# FIT_HDMI_X24-20.net
KiCad netlist of a schematic drawn in Altium Designer
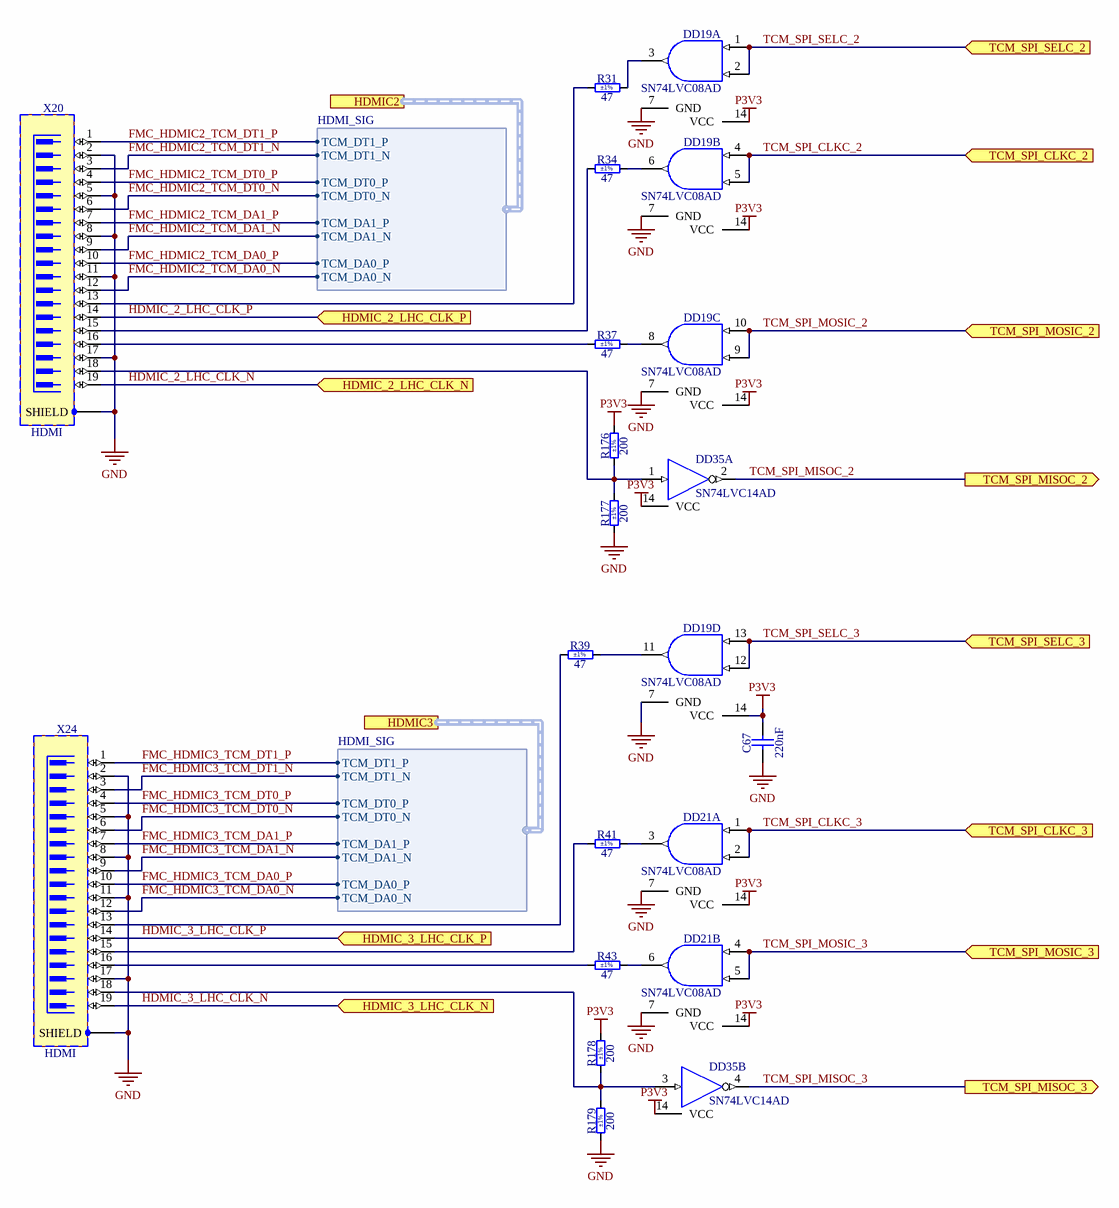
[diagram p0: FIT_HDMI_X24-20.SchDoc]

(export (version "E")
  (design (tool "Eeschema 10.0.6"))
  (components
    (comp (ref "C67")
      (value "220nF")
      (footprint "CAPC2012X135N")
      (description "Non-polarised capacitor")
      (fields
        (field (name "PART NUMBER") "CC0805_220NF_50V_10%_X7R")
        (field (name "VOLTAGE") "50V")
        (field (name "AUTHOR") "CERN DEM JLC")
      )
      (libsource (lib "Capacitors") (part "Capacitor - non polarized"))
    )
    (comp (ref "DD19")
      (value "SN74LVC08AD")
      (footprint "SOIC127P600X175-14N")
      (description "Quad 2-Input AND Gate")
      (fields (field (name "MANUFACTURER") "TEXAS INSTRUMENTS") (field (name "AUTHOR") "CERN DEM JLC"))
      (libsource (lib "ICs And Semiconductors") (part "7408"))
    )
    (comp (ref "DD21")
      (value "SN74LVC08AD")
      (footprint "SOIC127P600X175-14N")
      (description "Quad 2-Input AND Gate")
      (fields (field (name "MANUFACTURER") "TEXAS INSTRUMENTS") (field (name "AUTHOR") "CERN DEM JLC"))
      (libsource (lib "ICs And Semiconductors") (part "7408"))
    )
    (comp (ref "DD35")
      (value "SN74LVC14AD")
      (footprint "SOIC127P600X175-14N")
      (description "Hex Schmitt-Trigger Inverter")
      (fields (field (name "MANUFACTURER") "TEXAS INSTRUMENTS") (field (name "AUTHOR") "CERN DEM JMW"))
      (libsource (lib "ICs And Semiconductors") (part "7414"))
    )
    (comp (ref "R31")
      (value "47")
      (footprint "RESC2012X60N")
      (description "Resistor - 1%")
      (fields
        (field (name "TOLERANCE") "±1%")
        (field (name "PART NUMBER") "R0805_47R_1%_0.125W_100PPM")
        (field (name "POWER") "0.125W")
        (field (name "AUTHOR") "CERN DEM JLC")
      )
      (libsource (lib "Resistors") (part "Resistor - 1%"))
    )
    (comp (ref "R34")
      (value "47")
      (footprint "RESC2012X60N")
      (description "Resistor - 1%")
      (fields
        (field (name "TOLERANCE") "±1%")
        (field (name "PART NUMBER") "R0805_47R_1%_0.125W_100PPM")
        (field (name "POWER") "0.125W")
        (field (name "AUTHOR") "CERN DEM JLC")
      )
      (libsource (lib "Resistors") (part "Resistor - 1%"))
    )
    (comp (ref "R37")
      (value "47")
      (footprint "RESC2012X60N")
      (description "Resistor - 1%")
      (fields
        (field (name "TOLERANCE") "±1%")
        (field (name "PART NUMBER") "R0805_47R_1%_0.125W_100PPM")
        (field (name "POWER") "0.125W")
        (field (name "AUTHOR") "CERN DEM JLC")
      )
      (libsource (lib "Resistors") (part "Resistor - 1%"))
    )
    (comp (ref "R39")
      (value "47")
      (footprint "RESC2012X60N")
      (description "Resistor - 1%")
      (fields
        (field (name "TOLERANCE") "±1%")
        (field (name "PART NUMBER") "R0805_47R_1%_0.125W_100PPM")
        (field (name "POWER") "0.125W")
        (field (name "AUTHOR") "CERN DEM JLC")
      )
      (libsource (lib "Resistors") (part "Resistor - 1%"))
    )
    (comp (ref "R41")
      (value "47")
      (footprint "RESC2012X60N")
      (description "Resistor - 1%")
      (fields
        (field (name "TOLERANCE") "±1%")
        (field (name "PART NUMBER") "R0805_47R_1%_0.125W_100PPM")
        (field (name "POWER") "0.125W")
        (field (name "AUTHOR") "CERN DEM JLC")
      )
      (libsource (lib "Resistors") (part "Resistor - 1%"))
    )
    (comp (ref "R43")
      (value "47")
      (footprint "RESC2012X60N")
      (description "Resistor - 1%")
      (fields
        (field (name "TOLERANCE") "±1%")
        (field (name "PART NUMBER") "R0805_47R_1%_0.125W_100PPM")
        (field (name "POWER") "0.125W")
        (field (name "AUTHOR") "CERN DEM JLC")
      )
      (libsource (lib "Resistors") (part "Resistor - 1%"))
    )
    (comp (ref "R176")
      (value "200")
      (footprint "RESC2012X60N")
      (description "Resistor - 1%")
      (fields
        (field (name "TOLERANCE") "±1%")
        (field (name "PART NUMBER") "R0805_200R_1%_0.125W_100PPM")
        (field (name "POWER") "0.125W")
        (field (name "AUTHOR") "CERN DEM JLC")
      )
      (libsource (lib "Resistors") (part "Resistor - 1%"))
    )
    (comp (ref "R177")
      (value "200")
      (footprint "RESC2012X60N")
      (description "Resistor - 1%")
      (fields
        (field (name "TOLERANCE") "±1%")
        (field (name "PART NUMBER") "R0805_200R_1%_0.125W_100PPM")
        (field (name "POWER") "0.125W")
        (field (name "AUTHOR") "CERN DEM JLC")
      )
      (libsource (lib "Resistors") (part "Resistor - 1%"))
    )
    (comp (ref "R178")
      (value "200")
      (footprint "RESC2012X60N")
      (description "Resistor - 1%")
      (fields
        (field (name "TOLERANCE") "±1%")
        (field (name "PART NUMBER") "R0805_200R_1%_0.125W_100PPM")
        (field (name "POWER") "0.125W")
        (field (name "AUTHOR") "CERN DEM JLC")
      )
      (libsource (lib "Resistors") (part "Resistor - 1%"))
    )
    (comp (ref "R179")
      (value "200")
      (footprint "RESC2012X60N")
      (description "Resistor - 1%")
      (fields
        (field (name "TOLERANCE") "±1%")
        (field (name "PART NUMBER") "R0805_200R_1%_0.125W_100PPM")
        (field (name "POWER") "0.125W")
        (field (name "AUTHOR") "CERN DEM JLC")
      )
      (libsource (lib "Resistors") (part "Resistor - 1%"))
    )
    (comp (ref "X20")
      (value "HDMI")
      (footprint "TYCO_2007435-1")
      (description "Connector HDMI 19 Male + 1 Shield")
      (fields
        (field (name "PART NUMBER") "TYCO_2007435-1")
        (field (name "MANUFACTURER") "TYCO ELECTRONICS")
        (field (name "AUTHOR") "CERN DEM MR")
      )
      (libsource (lib "Connectors") (part "Connector HDMI 19 Male + 1 Shield"))
    )
    (comp (ref "X24")
      (value "HDMI")
      (footprint "TYCO_2007435-1")
      (description "Connector HDMI 19 Male + 1 Shield")
      (fields
        (field (name "PART NUMBER") "TYCO_2007435-1")
        (field (name "MANUFACTURER") "TYCO ELECTRONICS")
        (field (name "AUTHOR") "CERN DEM MR")
      )
      (libsource (lib "Connectors") (part "Connector HDMI 19 Male + 1 Shield"))
    )
  )
  (nets
    (net (code "2") (name "/FMC_HDMIC2_TCM_DA0_N") (class "Default")
      (node (ref "X20") (pin "12") (pinfunction "12_12") (pintype "bidirectional"))
    )
    (net (code "3") (name "/FMC_HDMIC2_TCM_DA0_P") (class "Default")
      (node (ref "X20") (pin "10") (pinfunction "10_10") (pintype "bidirectional"))
    )
    (net (code "4") (name "/FMC_HDMIC2_TCM_DA1_N") (class "Default")
      (node (ref "X20") (pin "9") (pinfunction "9_9") (pintype "bidirectional"))
    )
    (net (code "5") (name "/FMC_HDMIC2_TCM_DA1_P") (class "Default")
      (node (ref "X20") (pin "7") (pinfunction "7_7") (pintype "bidirectional"))
    )
    (net (code "6") (name "/FMC_HDMIC2_TCM_DT0_N") (class "Default")
      (node (ref "X20") (pin "6") (pinfunction "6_6") (pintype "bidirectional"))
    )
    (net (code "7") (name "/FMC_HDMIC2_TCM_DT0_P") (class "Default")
      (node (ref "X20") (pin "4") (pinfunction "4_4") (pintype "bidirectional"))
    )
    (net (code "8") (name "/FMC_HDMIC2_TCM_DT1_N") (class "Default")
      (node (ref "X20") (pin "3") (pinfunction "3_3") (pintype "bidirectional"))
    )
    (net (code "9") (name "/FMC_HDMIC2_TCM_DT1_P") (class "Default")
      (node (ref "X20") (pin "1") (pinfunction "1_1") (pintype "bidirectional"))
    )
    (net (code "10") (name "/FMC_HDMIC3_TCM_DA0_N") (class "Default")
      (node (ref "X24") (pin "12") (pinfunction "12_12") (pintype "bidirectional"))
    )
    (net (code "11") (name "/FMC_HDMIC3_TCM_DA0_P") (class "Default")
      (node (ref "X24") (pin "10") (pinfunction "10_10") (pintype "bidirectional"))
    )
    (net (code "12") (name "/FMC_HDMIC3_TCM_DA1_N") (class "Default")
      (node (ref "X24") (pin "9") (pinfunction "9_9") (pintype "bidirectional"))
    )
    (net (code "13") (name "/FMC_HDMIC3_TCM_DA1_P") (class "Default")
      (node (ref "X24") (pin "7") (pinfunction "7_7") (pintype "bidirectional"))
    )
    (net (code "14") (name "/FMC_HDMIC3_TCM_DT0_N") (class "Default")
      (node (ref "X24") (pin "6") (pinfunction "6_6") (pintype "bidirectional"))
    )
    (net (code "15") (name "/FMC_HDMIC3_TCM_DT0_P") (class "Default")
      (node (ref "X24") (pin "4") (pinfunction "4_4") (pintype "bidirectional"))
    )
    (net (code "16") (name "/FMC_HDMIC3_TCM_DT1_N") (class "Default")
      (node (ref "X24") (pin "3") (pinfunction "3_3") (pintype "bidirectional"))
    )
    (net (code "17") (name "/FMC_HDMIC3_TCM_DT1_P") (class "Default")
      (node (ref "X24") (pin "1") (pinfunction "1_1") (pintype "bidirectional"))
    )
    (net (code "18") (name "/HDMIC_2_LHC_CLK_N") (class "Default")
      (node (ref "X20") (pin "19") (pinfunction "19_19") (pintype "bidirectional"))
    )
    (net (code "19") (name "/HDMIC_2_LHC_CLK_P") (class "Default")
      (node (ref "X20") (pin "14") (pinfunction "14_14") (pintype "bidirectional"))
    )
    (net (code "20") (name "/HDMIC_3_LHC_CLK_N") (class "Default")
      (node (ref "X24") (pin "19") (pinfunction "19_19") (pintype "bidirectional"))
    )
    (net (code "21") (name "/HDMIC_3_LHC_CLK_P") (class "Default")
      (node (ref "X24") (pin "14") (pinfunction "14_14") (pintype "bidirectional"))
    )
    (net (code "22") (name "/TCM_SPI_CLKC_2") (class "Default")
      (node (ref "DD19") (pin "4") (pinfunction "A_4") (pintype "input"))
      (node (ref "DD19") (pin "5") (pinfunction "B_5") (pintype "input"))
    )
    (net (code "23") (name "/TCM_SPI_CLKC_3") (class "Default")
      (node (ref "DD21") (pin "1") (pinfunction "A_1") (pintype "input"))
      (node (ref "DD21") (pin "2") (pinfunction "B_2") (pintype "input"))
    )
    (net (code "24") (name "/TCM_SPI_MISOC_2") (class "Default")
      (node (ref "DD35") (pin "2") (pinfunction "OUT_2") (pintype "output"))
    )
    (net (code "25") (name "/TCM_SPI_MISOC_3") (class "Default")
      (node (ref "DD35") (pin "4") (pinfunction "OUT_4") (pintype "output"))
    )
    (net (code "26") (name "/TCM_SPI_MOSIC_2") (class "Default")
      (node (ref "DD19") (pin "10") (pinfunction "A_10") (pintype "input"))
      (node (ref "DD19") (pin "9") (pinfunction "B_9") (pintype "input"))
    )
    (net (code "27") (name "/TCM_SPI_MOSIC_3") (class "Default")
      (node (ref "DD21") (pin "4") (pinfunction "A_4") (pintype "input"))
      (node (ref "DD21") (pin "5") (pinfunction "B_5") (pintype "input"))
    )
    (net (code "28") (name "/TCM_SPI_SELC_2") (class "Default")
      (node (ref "DD19") (pin "1") (pinfunction "A_1") (pintype "input"))
      (node (ref "DD19") (pin "2") (pinfunction "B_2") (pintype "input"))
    )
    (net (code "29") (name "/TCM_SPI_SELC_3") (class "Default")
      (node (ref "DD19") (pin "12") (pinfunction "B_12") (pintype "input"))
      (node (ref "DD19") (pin "13") (pinfunction "A_13") (pintype "input"))
    )
    (net (code "31") (name "GND") (class "Default")
      (node (ref "C67") (pin "1") (pinfunction "1_1") (pintype "passive"))
      (node (ref "DD19") (pin "7") (pinfunction "GND_7") (pintype "power_in"))
      (node (ref "DD21") (pin "7") (pinfunction "GND_7") (pintype "power_in"))
      (node (ref "DD35") (pin "7") (pinfunction "GND_7") (pintype "power_in"))
      (node (ref "R177") (pin "1") (pinfunction "1_1") (pintype "passive"))
      (node (ref "R179") (pin "1") (pinfunction "1_1") (pintype "passive"))
      (node (ref "X20") (pin "11") (pinfunction "11_11") (pintype "bidirectional"))
      (node (ref "X20") (pin "17") (pinfunction "17_17") (pintype "bidirectional"))
      (node (ref "X20") (pin "2") (pinfunction "2_2") (pintype "bidirectional"))
      (node (ref "X20") (pin "5") (pinfunction "5_5") (pintype "bidirectional"))
      (node (ref "X20") (pin "8") (pinfunction "8_8") (pintype "bidirectional"))
      (node (ref "X20") (pin "SHIELD") (pinfunction "SHIELD_SHIELD") (pintype "power_in"))
      (node (ref "X24") (pin "11") (pinfunction "11_11") (pintype "bidirectional"))
      (node (ref "X24") (pin "17") (pinfunction "17_17") (pintype "bidirectional"))
      (node (ref "X24") (pin "2") (pinfunction "2_2") (pintype "bidirectional"))
      (node (ref "X24") (pin "5") (pinfunction "5_5") (pintype "bidirectional"))
      (node (ref "X24") (pin "8") (pinfunction "8_8") (pintype "bidirectional"))
      (node (ref "X24") (pin "SHIELD") (pinfunction "SHIELD_SHIELD") (pintype "power_in"))
    )
    (net (code "32") (name "Net-(DD19A-Y)") (class "Default")
      (node (ref "DD19") (pin "3") (pinfunction "Y_3") (pintype "output"))
      (node (ref "R31") (pin "2") (pinfunction "2_2") (pintype "passive"))
    )
    (net (code "33") (name "Net-(DD19B-Y)") (class "Default")
      (node (ref "DD19") (pin "6") (pinfunction "Y_6") (pintype "output"))
      (node (ref "R34") (pin "2") (pinfunction "2_2") (pintype "passive"))
    )
    (net (code "34") (name "Net-(DD19C-Y)") (class "Default")
      (node (ref "DD19") (pin "8") (pinfunction "Y_8") (pintype "output"))
      (node (ref "R37") (pin "2") (pinfunction "2_2") (pintype "passive"))
    )
    (net (code "35") (name "Net-(DD19D-Y)") (class "Default")
      (node (ref "DD19") (pin "11") (pinfunction "Y_11") (pintype "output"))
      (node (ref "R39") (pin "2") (pinfunction "2_2") (pintype "passive"))
    )
    (net (code "36") (name "Net-(DD21A-Y)") (class "Default")
      (node (ref "DD21") (pin "3") (pinfunction "Y_3") (pintype "output"))
      (node (ref "R41") (pin "2") (pinfunction "2_2") (pintype "passive"))
    )
    (net (code "37") (name "Net-(DD21B-Y)") (class "Default")
      (node (ref "DD21") (pin "6") (pinfunction "Y_6") (pintype "output"))
      (node (ref "R43") (pin "2") (pinfunction "2_2") (pintype "passive"))
    )
    (net (code "38") (name "Net-(DD35A-IN)") (class "Default")
      (node (ref "DD35") (pin "1") (pinfunction "IN_1") (pintype "input"))
      (node (ref "R176") (pin "1") (pinfunction "1_1") (pintype "passive"))
      (node (ref "R177") (pin "2") (pinfunction "2_2") (pintype "passive"))
      (node (ref "X20") (pin "18") (pinfunction "18_18") (pintype "bidirectional"))
    )
    (net (code "39") (name "Net-(DD35B-IN)") (class "Default")
      (node (ref "DD35") (pin "3") (pinfunction "IN_3") (pintype "input"))
      (node (ref "R178") (pin "1") (pinfunction "1_1") (pintype "passive"))
      (node (ref "R179") (pin "2") (pinfunction "2_2") (pintype "passive"))
      (node (ref "X24") (pin "18") (pinfunction "18_18") (pintype "bidirectional"))
    )
    (net (code "40") (name "Net-(R31-Pad1)") (class "Default")
      (node (ref "R31") (pin "1") (pinfunction "1_1") (pintype "passive"))
      (node (ref "X20") (pin "13") (pinfunction "13_13") (pintype "bidirectional"))
    )
    (net (code "41") (name "Net-(R34-Pad1)") (class "Default")
      (node (ref "R34") (pin "1") (pinfunction "1_1") (pintype "passive"))
      (node (ref "X20") (pin "15") (pinfunction "15_15") (pintype "bidirectional"))
    )
    (net (code "42") (name "Net-(R37-Pad1)") (class "Default")
      (node (ref "R37") (pin "1") (pinfunction "1_1") (pintype "passive"))
      (node (ref "X20") (pin "16") (pinfunction "16_16") (pintype "bidirectional"))
    )
    (net (code "43") (name "Net-(R39-Pad1)") (class "Default")
      (node (ref "R39") (pin "1") (pinfunction "1_1") (pintype "passive"))
      (node (ref "X24") (pin "13") (pinfunction "13_13") (pintype "bidirectional"))
    )
    (net (code "44") (name "Net-(R41-Pad1)") (class "Default")
      (node (ref "R41") (pin "1") (pinfunction "1_1") (pintype "passive"))
      (node (ref "X24") (pin "15") (pinfunction "15_15") (pintype "bidirectional"))
    )
    (net (code "45") (name "Net-(R43-Pad1)") (class "Default")
      (node (ref "R43") (pin "1") (pinfunction "1_1") (pintype "passive"))
      (node (ref "X24") (pin "16") (pinfunction "16_16") (pintype "bidirectional"))
    )
    (net (code "46") (name "P3V3") (class "Default")
      (node (ref "C67") (pin "2") (pinfunction "2_2") (pintype "passive"))
      (node (ref "DD19") (pin "14") (pinfunction "VCC_14") (pintype "power_in"))
      (node (ref "DD21") (pin "14") (pinfunction "VCC_14") (pintype "power_in"))
      (node (ref "DD35") (pin "14") (pinfunction "VCC_14") (pintype "power_in"))
      (node (ref "R176") (pin "2") (pinfunction "2_2") (pintype "passive"))
      (node (ref "R178") (pin "2") (pinfunction "2_2") (pintype "passive"))
    )
  )
)
